# dc_part.net
KiCad netlist of a schematic drawn in EAGLE
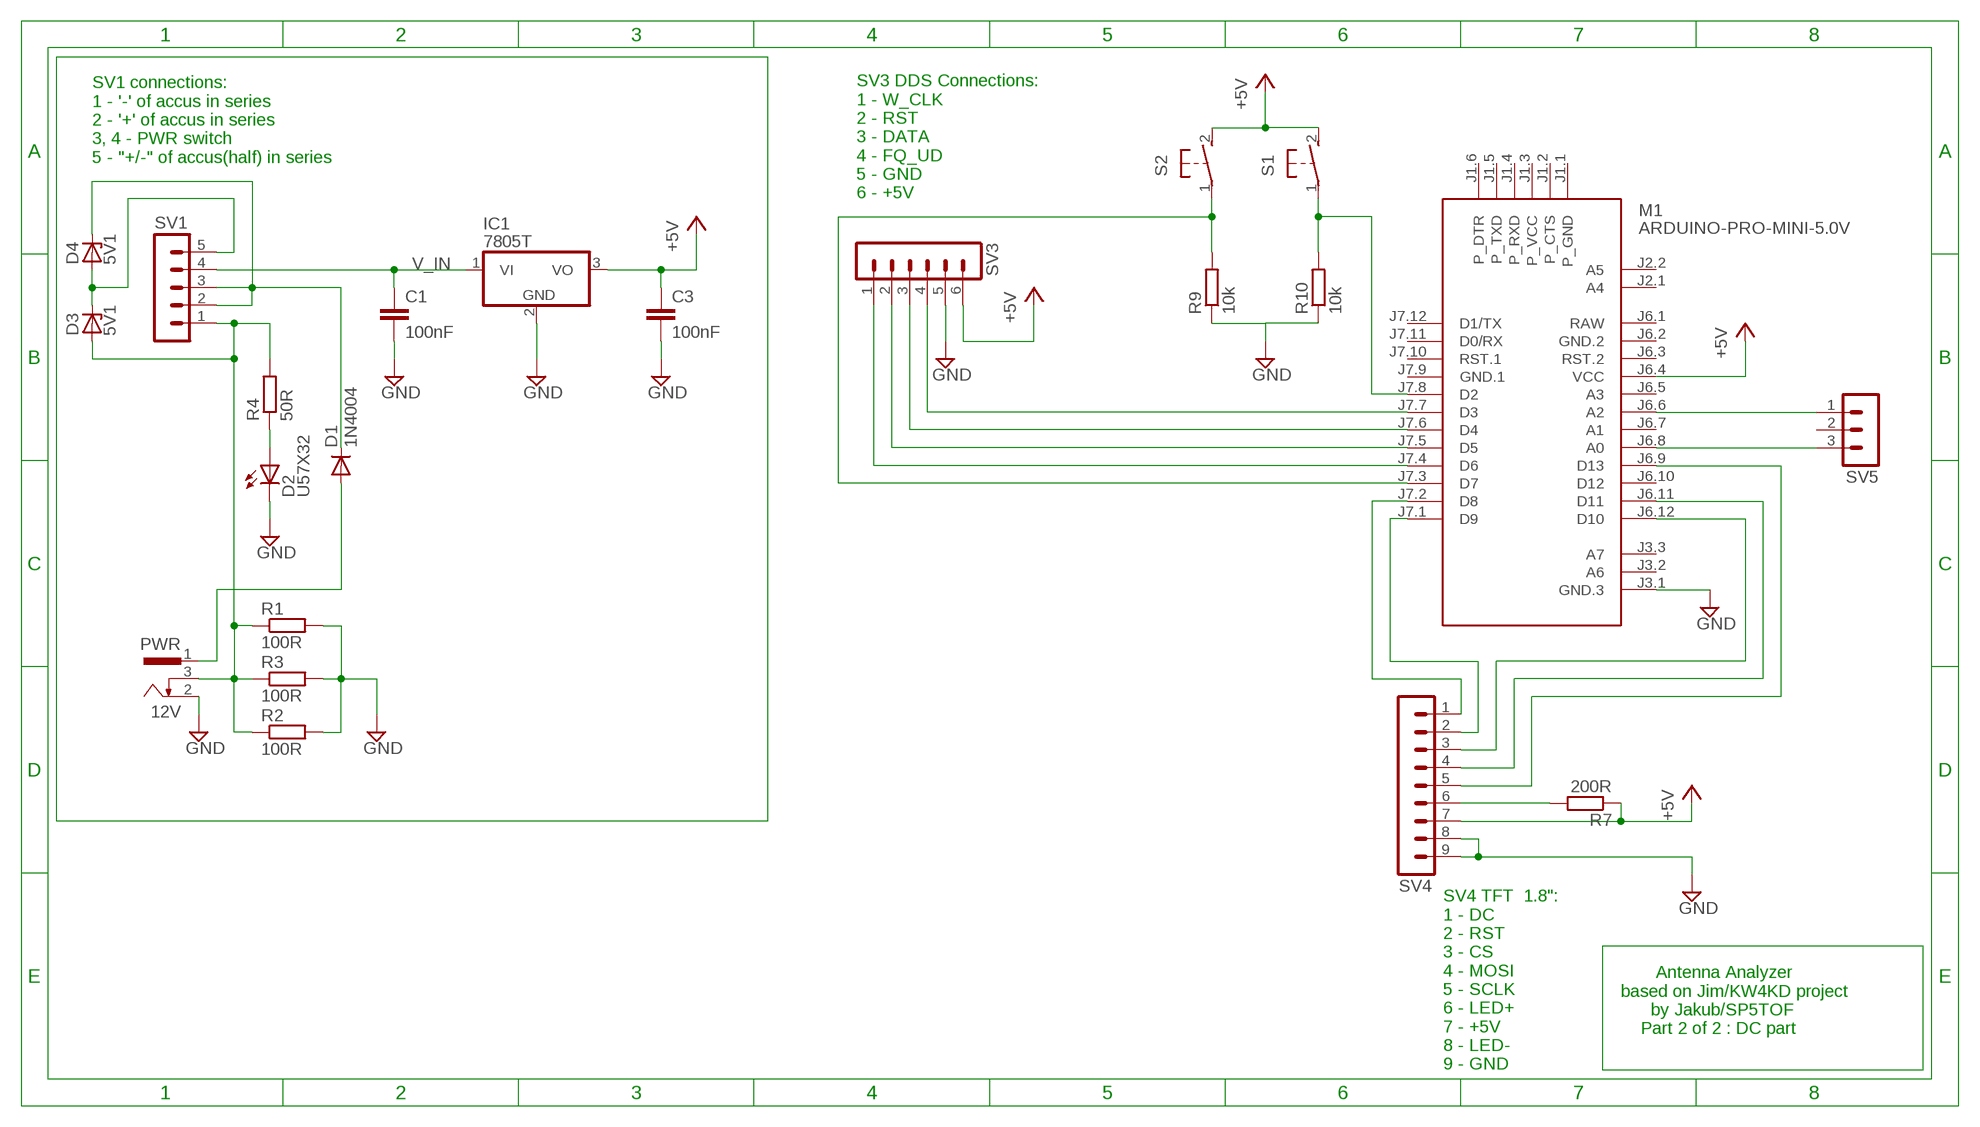
[diagram p0: schematic, sheet 1]

(export (version "E")
  (design (tool "Eeschema 10.0.6"))
  (components
    (comp (ref "C1")
      (value "100nF")
      (footprint "eagle-import:C050-024X044")
      (libsource (lib "eagle-import") (part "C-EU050-024X044"))
    )
    (comp (ref "C3")
      (value "100nF")
      (footprint "eagle-import:C050-024X044")
      (libsource (lib "eagle-import") (part "C-EU050-024X044"))
    )
    (comp (ref "D1")
      (value "1N4004")
      (footprint "eagle-import:DO41-10")
      (libsource (lib "eagle-import") (part "1N4004"))
    )
    (comp (ref "D2")
      (value "U57X32")
      (footprint "eagle-import:U57X32")
      (libsource (lib "eagle-import") (part "U57X32"))
    )
    (comp (ref "D3")
      (value "5V1")
      (footprint "eagle-import:ZDIO-5")
      (libsource (lib "eagle-import") (part "ZENER-DIODEZD-5"))
    )
    (comp (ref "D4")
      (value "5V1")
      (footprint "eagle-import:ZDIO-5")
      (libsource (lib "eagle-import") (part "ZENER-DIODEZD-5"))
    )
    (comp (ref "IC1")
      (value "7805T")
      (footprint "eagle-import:TO220H")
      (libsource (lib "eagle-import") (part "78T05"))
    )
    (comp (ref "M1")
      (value "ARDUINO-PRO-MINI-5.0V")
      (footprint "eagle-import:ARDUINO-PRO-MINI")
      (libsource (lib "eagle-import") (part "ARDUINO-PRO-MINI-5.0V"))
    )
    (comp (ref "PWR")
      (value "12V")
      (footprint "eagle-import:733980-62")
      (libsource (lib "eagle-import") (part "73398?0-62"))
    )
    (comp (ref "R1")
      (value "100R")
      (footprint "eagle-import:0207_10")
      (libsource (lib "eagle-import") (part "R-EU_0207/10"))
    )
    (comp (ref "R2")
      (value "100R")
      (footprint "eagle-import:0207_10")
      (libsource (lib "eagle-import") (part "R-EU_0207/10"))
    )
    (comp (ref "R3")
      (value "100R")
      (footprint "eagle-import:0207_10")
      (libsource (lib "eagle-import") (part "R-EU_0207/10"))
    )
    (comp (ref "R4")
      (value "50R")
      (footprint "eagle-import:0207_10")
      (libsource (lib "eagle-import") (part "R-EU_0207/10"))
    )
    (comp (ref "R7")
      (value "200R")
      (footprint "eagle-import:0207_10")
      (libsource (lib "eagle-import") (part "R-EU_0207/10"))
    )
    (comp (ref "R9")
      (value "10k")
      (footprint "eagle-import:0207_10")
      (libsource (lib "eagle-import") (part "R-EU_0207/10"))
    )
    (comp (ref "R10")
      (value "10k")
      (footprint "eagle-import:0207_10")
      (libsource (lib "eagle-import") (part "R-EU_0207/10"))
    )
    (comp (ref "S1")
      (value "31-XX")
      (footprint "eagle-import:B3F-31XX")
      (fields (field (name "MPN") "B3F-3100"))
      (libsource (lib "eagle-import") (part "31-XX"))
    )
    (comp (ref "S2")
      (value "31-XX")
      (footprint "eagle-import:B3F-31XX")
      (fields (field (name "MPN") "B3F-3100"))
      (libsource (lib "eagle-import") (part "31-XX"))
    )
    (comp (ref "SV1")
      (value "MA05-1")
      (footprint "eagle-import:MA05-1")
      (libsource (lib "eagle-import") (part "MA05-1"))
    )
    (comp (ref "SV3")
      (value "MA06-1")
      (footprint "eagle-import:MA06-1")
      (libsource (lib "eagle-import") (part "MA06-1"))
    )
    (comp (ref "SV4")
      (value "MA09-1")
      (footprint "eagle-import:MA09-1")
      (libsource (lib "eagle-import") (part "MA09-1"))
    )
    (comp (ref "SV5")
      (value "MA03-1")
      (footprint "eagle-import:MA03-1")
      (libsource (lib "eagle-import") (part "MA03-1"))
    )
  )
  (nets
    (net (code "1") (name "+5V") (class "Default")
      (node (ref "C3") (pin "1") (pinfunction "1_1") (pintype "passive"))
      (node (ref "IC1") (pin "3") (pinfunction "VO_3") (pintype "passive"))
      (node (ref "M1") (pin "J6.4") (pinfunction "VCC_J6.4") (pintype "power_in"))
      (node (ref "R7") (pin "1") (pinfunction "1_1") (pintype "passive"))
      (node (ref "S1") (pin "2") (pinfunction "S_2") (pintype "passive"))
      (node (ref "S2") (pin "2") (pinfunction "S_2") (pintype "passive"))
      (node (ref "SV3") (pin "6") (pinfunction "6_6") (pintype "passive"))
      (node (ref "SV4") (pin "7") (pinfunction "7_7") (pintype "passive"))
    )
    (net (code "2") (name "/GND.1") (class "Default")
      (node (ref "M1") (pin "J7.9") (pinfunction "GND.1_J7.9") (pintype "power_in"))
    )
    (net (code "3") (name "/GND.2") (class "Default")
      (node (ref "M1") (pin "J6.2") (pinfunction "GND.2_J6.2") (pintype "power_in"))
    )
    (net (code "4") (name "/RAW") (class "Default")
      (node (ref "M1") (pin "J6.1") (pinfunction "RAW_J6.1") (pintype "power_in"))
    )
    (net (code "5") (name "/V_IN") (class "Default")
      (node (ref "C1") (pin "1") (pinfunction "1_1") (pintype "passive"))
      (node (ref "IC1") (pin "1") (pinfunction "VI_1") (pintype "input"))
      (node (ref "SV1") (pin "4") (pinfunction "4_4") (pintype "passive"))
    )
    (net (code "6") (name "GND") (class "Default")
      (node (ref "C1") (pin "2") (pinfunction "2_2") (pintype "passive"))
      (node (ref "C3") (pin "2") (pinfunction "2_2") (pintype "passive"))
      (node (ref "D2") (pin "K") (pinfunction "C_K") (pintype "passive"))
      (node (ref "IC1") (pin "2") (pinfunction "GND_2") (pintype "passive"))
      (node (ref "M1") (pin "J3.1") (pinfunction "GND.3_J3.1") (pintype "bidirectional"))
      (node (ref "PWR") (pin "2") (pinfunction "2_2") (pintype "passive"))
      (node (ref "R1") (pin "2") (pinfunction "2_2") (pintype "passive"))
      (node (ref "R10") (pin "1") (pinfunction "1_1") (pintype "passive"))
      (node (ref "R2") (pin "2") (pinfunction "2_2") (pintype "passive"))
      (node (ref "R3") (pin "2") (pinfunction "2_2") (pintype "passive"))
      (node (ref "R9") (pin "1") (pinfunction "1_1") (pintype "passive"))
      (node (ref "SV3") (pin "5") (pinfunction "5_5") (pintype "passive"))
      (node (ref "SV4") (pin "8") (pinfunction "8_8") (pintype "passive"))
      (node (ref "SV4") (pin "9") (pinfunction "9_9") (pintype "passive"))
    )
    (net (code "7") (name "Net-(D1-PadA)") (class "Default")
      (node (ref "D1") (pin "A") (pinfunction "A_A") (pintype "passive"))
      (node (ref "PWR") (pin "1") (pinfunction "1_1") (pintype "passive"))
    )
    (net (code "8") (name "Net-(D1-PadC)") (class "Default")
      (node (ref "D1") (pin "C") (pinfunction "C_C") (pintype "passive"))
      (node (ref "D4") (pin "C") (pinfunction "C_C") (pintype "passive"))
      (node (ref "SV1") (pin "2") (pinfunction "2_2") (pintype "passive"))
      (node (ref "SV1") (pin "3") (pinfunction "3_3") (pintype "passive"))
    )
    (net (code "9") (name "Net-(D2-PadA)") (class "Default")
      (node (ref "D2") (pin "A") (pinfunction "A_A") (pintype "passive"))
      (node (ref "R4") (pin "1") (pinfunction "1_1") (pintype "passive"))
    )
    (net (code "10") (name "Net-(D3-PadA)") (class "Default")
      (node (ref "D3") (pin "A") (pinfunction "A_A") (pintype "passive"))
      (node (ref "PWR") (pin "3") (pinfunction "3_3") (pintype "passive"))
      (node (ref "R1") (pin "1") (pinfunction "1_1") (pintype "passive"))
      (node (ref "R2") (pin "1") (pinfunction "1_1") (pintype "passive"))
      (node (ref "R3") (pin "1") (pinfunction "1_1") (pintype "passive"))
      (node (ref "R4") (pin "2") (pinfunction "2_2") (pintype "passive"))
      (node (ref "SV1") (pin "1") (pinfunction "1_1") (pintype "passive"))
    )
    (net (code "11") (name "Net-(D3-PadC)") (class "Default")
      (node (ref "D3") (pin "C") (pinfunction "C_C") (pintype "passive"))
      (node (ref "D4") (pin "A") (pinfunction "A_A") (pintype "passive"))
      (node (ref "SV1") (pin "5") (pinfunction "5_5") (pintype "passive"))
    )
    (net (code "12") (name "Net-(M1-A0)") (class "Default")
      (node (ref "M1") (pin "J6.8") (pinfunction "A0_J6.8") (pintype "bidirectional"))
      (node (ref "SV5") (pin "3") (pinfunction "3_3") (pintype "passive"))
    )
    (net (code "13") (name "Net-(M1-A2)") (class "Default")
      (node (ref "M1") (pin "J6.6") (pinfunction "A2_J6.6") (pintype "bidirectional"))
      (node (ref "SV5") (pin "1") (pinfunction "1_1") (pintype "passive"))
    )
    (net (code "14") (name "Net-(M1-D2)") (class "Default")
      (node (ref "M1") (pin "J7.8") (pinfunction "D2_J7.8") (pintype "bidirectional"))
      (node (ref "R10") (pin "2") (pinfunction "2_2") (pintype "passive"))
      (node (ref "S1") (pin "1") (pinfunction "P_1") (pintype "passive"))
    )
    (net (code "15") (name "Net-(M1-D3)") (class "Default")
      (node (ref "M1") (pin "J7.7") (pinfunction "D3_J7.7") (pintype "bidirectional"))
      (node (ref "SV3") (pin "4") (pinfunction "4_4") (pintype "passive"))
    )
    (net (code "16") (name "Net-(M1-D4)") (class "Default")
      (node (ref "M1") (pin "J7.6") (pinfunction "D4_J7.6") (pintype "bidirectional"))
      (node (ref "SV3") (pin "3") (pinfunction "3_3") (pintype "passive"))
    )
    (net (code "17") (name "Net-(M1-D5)") (class "Default")
      (node (ref "M1") (pin "J7.5") (pinfunction "D5_J7.5") (pintype "bidirectional"))
      (node (ref "SV3") (pin "2") (pinfunction "2_2") (pintype "passive"))
    )
    (net (code "18") (name "Net-(M1-D6)") (class "Default")
      (node (ref "M1") (pin "J7.4") (pinfunction "D6_J7.4") (pintype "bidirectional"))
      (node (ref "SV3") (pin "1") (pinfunction "1_1") (pintype "passive"))
    )
    (net (code "19") (name "Net-(M1-D7)") (class "Default")
      (node (ref "M1") (pin "J7.3") (pinfunction "D7_J7.3") (pintype "bidirectional"))
      (node (ref "R9") (pin "2") (pinfunction "2_2") (pintype "passive"))
      (node (ref "S2") (pin "1") (pinfunction "P_1") (pintype "passive"))
    )
    (net (code "20") (name "Net-(M1-D8)") (class "Default")
      (node (ref "M1") (pin "J7.2") (pinfunction "D8_J7.2") (pintype "bidirectional"))
      (node (ref "SV4") (pin "1") (pinfunction "1_1") (pintype "passive"))
    )
    (net (code "21") (name "Net-(M1-D9)") (class "Default")
      (node (ref "M1") (pin "J7.1") (pinfunction "D9_J7.1") (pintype "bidirectional"))
      (node (ref "SV4") (pin "2") (pinfunction "2_2") (pintype "passive"))
    )
    (net (code "22") (name "Net-(M1-D10)") (class "Default")
      (node (ref "M1") (pin "J6.12") (pinfunction "D10_J6.12") (pintype "bidirectional"))
      (node (ref "SV4") (pin "3") (pinfunction "3_3") (pintype "passive"))
    )
    (net (code "23") (name "Net-(M1-D11)") (class "Default")
      (node (ref "M1") (pin "J6.11") (pinfunction "D11_J6.11") (pintype "bidirectional"))
      (node (ref "SV4") (pin "4") (pinfunction "4_4") (pintype "passive"))
    )
    (net (code "24") (name "Net-(M1-D13)") (class "Default")
      (node (ref "M1") (pin "J6.9") (pinfunction "D13_J6.9") (pintype "bidirectional"))
      (node (ref "SV4") (pin "5") (pinfunction "5_5") (pintype "passive"))
    )
    (net (code "25") (name "Net-(R7-Pad2)") (class "Default")
      (node (ref "R7") (pin "2") (pinfunction "2_2") (pintype "passive"))
      (node (ref "SV4") (pin "6") (pinfunction "6_6") (pintype "passive"))
    )
    (net (code "26") (name "unconnected-(M1-A1-PadJ6.7)") (class "Default")
      (node (ref "M1") (pin "J6.7") (pinfunction "A1_J6.7") (pintype "bidirectional"))
    )
    (net (code "27") (name "unconnected-(M1-A3-PadJ6.5)") (class "Default")
      (node (ref "M1") (pin "J6.5") (pinfunction "A3_J6.5") (pintype "bidirectional"))
    )
    (net (code "28") (name "unconnected-(M1-A4-PadJ2.1)") (class "Default")
      (node (ref "M1") (pin "J2.1") (pinfunction "A4_J2.1") (pintype "bidirectional"))
    )
    (net (code "29") (name "unconnected-(M1-A5-PadJ2.2)") (class "Default")
      (node (ref "M1") (pin "J2.2") (pinfunction "A5_J2.2") (pintype "bidirectional"))
    )
    (net (code "30") (name "unconnected-(M1-A6-PadJ3.2)") (class "Default")
      (node (ref "M1") (pin "J3.2") (pinfunction "A6_J3.2") (pintype "bidirectional"))
    )
    (net (code "31") (name "unconnected-(M1-A7-PadJ3.3)") (class "Default")
      (node (ref "M1") (pin "J3.3") (pinfunction "A7_J3.3") (pintype "bidirectional"))
    )
    (net (code "32") (name "unconnected-(M1-D0{slash}RX-PadJ7.11)") (class "Default")
      (node (ref "M1") (pin "J7.11") (pinfunction "D0/RX_J7.11") (pintype "bidirectional"))
    )
    (net (code "33") (name "unconnected-(M1-D1{slash}TX-PadJ7.12)") (class "Default")
      (node (ref "M1") (pin "J7.12") (pinfunction "D1/TX_J7.12") (pintype "bidirectional"))
    )
    (net (code "34") (name "unconnected-(M1-D12-PadJ6.10)") (class "Default")
      (node (ref "M1") (pin "J6.10") (pinfunction "D12_J6.10") (pintype "bidirectional"))
    )
    (net (code "35") (name "unconnected-(M1-P_CTS-PadJ1.2)") (class "Default")
      (node (ref "M1") (pin "J1.2") (pinfunction "P_CTS_J1.2") (pintype "bidirectional"))
    )
    (net (code "36") (name "unconnected-(M1-P_DTR-PadJ1.6)") (class "Default")
      (node (ref "M1") (pin "J1.6") (pinfunction "P_DTR_J1.6") (pintype "bidirectional"))
    )
    (net (code "37") (name "unconnected-(M1-P_GND-PadJ1.1)") (class "Default")
      (node (ref "M1") (pin "J1.1") (pinfunction "P_GND_J1.1") (pintype "bidirectional"))
    )
    (net (code "38") (name "unconnected-(M1-P_RXD-PadJ1.4)") (class "Default")
      (node (ref "M1") (pin "J1.4") (pinfunction "P_RXD_J1.4") (pintype "bidirectional"))
    )
    (net (code "39") (name "unconnected-(M1-P_TXD-PadJ1.5)") (class "Default")
      (node (ref "M1") (pin "J1.5") (pinfunction "P_TXD_J1.5") (pintype "bidirectional"))
    )
    (net (code "40") (name "unconnected-(M1-P_VCC-PadJ1.3)") (class "Default")
      (node (ref "M1") (pin "J1.3") (pinfunction "P_VCC_J1.3") (pintype "bidirectional"))
    )
    (net (code "41") (name "unconnected-(M1-RST.1-PadJ7.10)") (class "Default")
      (node (ref "M1") (pin "J7.10") (pinfunction "RST.1_J7.10") (pintype "bidirectional"))
    )
    (net (code "42") (name "unconnected-(M1-RST.2-PadJ6.3)") (class "Default")
      (node (ref "M1") (pin "J6.3") (pinfunction "RST.2_J6.3") (pintype "bidirectional"))
    )
    (net (code "43") (name "unconnected-(SV5-Pad2)") (class "Default")
      (node (ref "SV5") (pin "2") (pinfunction "2_2") (pintype "passive"))
    )
  )
)
